# Port.net
KiCad netlist of a schematic drawn in Altium Designer
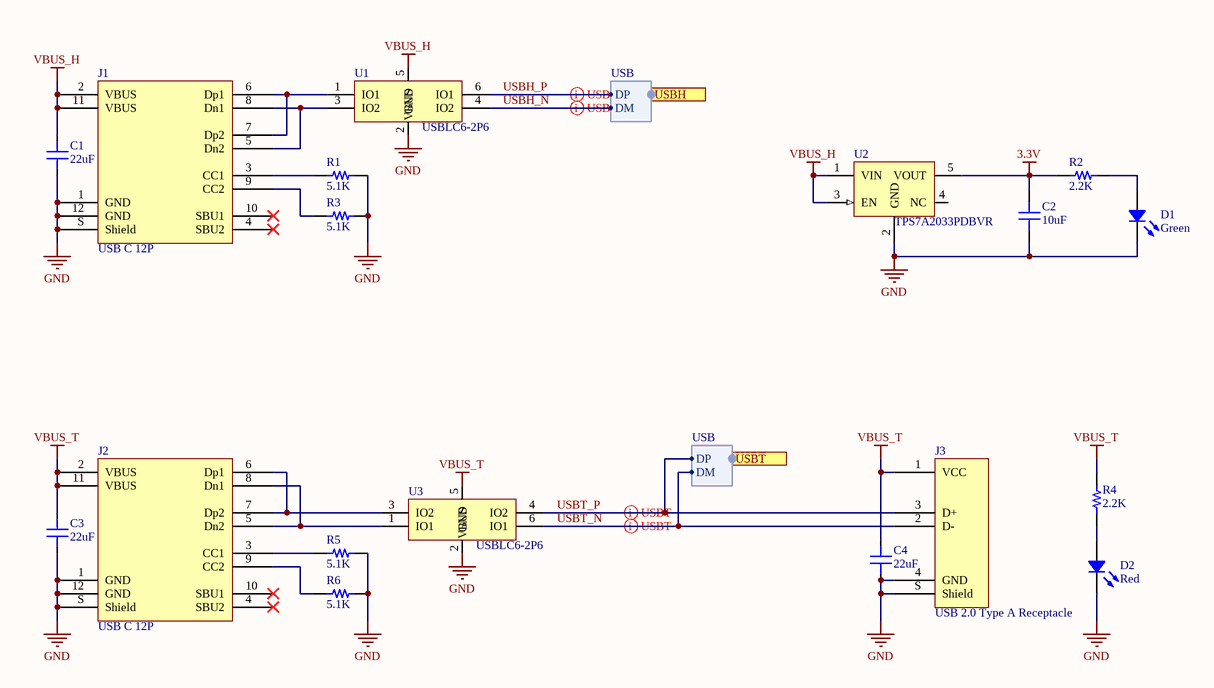
[diagram p0: Port.SchDoc]

(export (version "E")
  (design (tool "Eeschema 10.0.6"))
  (components
    (comp (ref "C1")
      (value "22uF")
      (footprint "CAP 0805/2012")
      (description "CAP CER 22UF 10V X5R 0805")
      (fields (field (name "PART NUMBER") "GRM219R61A226MEA0D") (field (name "MANUFACTURER") "Murata"))
      (libsource (lib "Mengsklib") (part "Capacitor"))
    )
    (comp (ref "C2")
      (value "10uF")
      (footprint "CAP 0603/1608")
      (description "CAP CER 10UF 25V X5R 0603")
      (fields (field (name "PART NUMBER") "GRM188R61E106MA73D") (field (name "MANUFACTURER") "Murata"))
      (libsource (lib "") (part "Capacitor_1"))
    )
    (comp (ref "C3")
      (value "22uF")
      (footprint "CAP 0805/2012")
      (description "CAP CER 22UF 10V X5R 0805")
      (fields (field (name "PART NUMBER") "GRM219R61A226MEA0D") (field (name "MANUFACTURER") "Murata"))
      (libsource (lib "Mengsklib") (part "Capacitor"))
    )
    (comp (ref "C4")
      (value "22uF")
      (footprint "CAP 0805/2012")
      (description "CAP CER 22UF 10V X5R 0805")
      (fields (field (name "PART NUMBER") "GRM219R61A226MEA0D") (field (name "MANUFACTURER") "Murata"))
      (libsource (lib "Mengsklib") (part "Capacitor"))
    )
    (comp (ref "D1")
      (value "Green")
      (footprint "LED 0603/1608 GREEN")
      (description "LED GREEN CLEAR 0603 SMD")
      (fields
        (field (name "COLOUR") "Green")
        (field (name "PART NUMBER") "LTST-C191KGKT")
        (field (name "MANUFACTURER") "Lite-On Inc.")
      )
      (libsource (lib "Mengsklib") (part "LED"))
    )
    (comp (ref "D2")
      (value "Red")
      (footprint "LED 0603/1608 RED")
      (description "LED RED CLEAR 0603 SMD")
      (fields
        (field (name "COLOUR") "Red")
        (field (name "PART NUMBER") "LTST-C191KRKT")
        (field (name "MANUFACTURER") "Lite-On Inc.")
      )
      (libsource (lib "Mengsklib") (part "LED"))
    )
    (comp (ref "J1")
      (value "USB C 12P")
      (footprint "JAE USB DX07S016JA1R1500")
      (description "USB 2.0 Type C, Receptacle, Horizontal, SMT")
      (fields (field (name "PART NUMBER") "DX07S016JA1R1500") (field (name "MANUFACTURER") "JAE"))
      (libsource (lib "Mengsklib") (part "JAE USB 2.0 Type C 12P"))
    )
    (comp (ref "J2")
      (value "USB C 12P")
      (footprint "JAE USB DX07S016JA1R1500")
      (description "USB 2.0 Type C, Receptacle, Horizontal, SMT")
      (fields (field (name "PART NUMBER") "DX07S016JA1R1500") (field (name "MANUFACTURER") "JAE"))
      (libsource (lib "Mengsklib") (part "JAE USB 2.0 Type C 12P"))
    )
    (comp (ref "J3")
      (value "USB 2.0 Type A Receptacle")
      (footprint "629104151021")
      (description "USB 2.0 Type A, Receptacle, Horizontal, SMT, with Pegs")
      (fields (field (name "PART NUMBER") "629104151021") (field (name "MANUFACTURER") "Wurth"))
      (libsource (lib "Mengsklib") (part "USB 2.0 Type A/B"))
    )
    (comp (ref "R1")
      (value "5.1K")
      (footprint "RES 0402/1005")
      (description "RES SMD 5.1K OHM 1% 1/16W 0402")
      (fields (field (name "PART NUMBER") "RC0402FR-075K1L") (field (name "MANUFACTURER") "Yageo"))
      (libsource (lib "Mengsklib") (part "Resistor"))
    )
    (comp (ref "R2")
      (value "2.2K")
      (footprint "RES 0402/1005")
      (description "RES SMD 2.2K OHM 1% 1/16W 0402")
      (fields (field (name "PART NUMBER") "RC0402FR-072K2L") (field (name "MANUFACTURER") "Yageo"))
      (libsource (lib "Mengsklib") (part "Resistor"))
    )
    (comp (ref "R3")
      (value "5.1K")
      (footprint "RES 0402/1005")
      (description "RES SMD 5.1K OHM 1% 1/16W 0402")
      (fields (field (name "PART NUMBER") "RC0402FR-075K1L") (field (name "MANUFACTURER") "Yageo"))
      (libsource (lib "Mengsklib") (part "Resistor"))
    )
    (comp (ref "R4")
      (value "2.2K")
      (footprint "RES 0402/1005")
      (description "RES SMD 2.2K OHM 1% 1/16W 0402")
      (fields (field (name "PART NUMBER") "RC0402FR-072K2L") (field (name "MANUFACTURER") "Yageo"))
      (libsource (lib "Mengsklib") (part "Resistor"))
    )
    (comp (ref "R5")
      (value "5.1K")
      (footprint "RES 0402/1005")
      (description "RES SMD 5.1K OHM 1% 1/16W 0402")
      (fields (field (name "PART NUMBER") "RC0402FR-075K1L") (field (name "MANUFACTURER") "Yageo"))
      (libsource (lib "Mengsklib") (part "Resistor"))
    )
    (comp (ref "R6")
      (value "5.1K")
      (footprint "RES 0402/1005")
      (description "RES SMD 5.1K OHM 1% 1/16W 0402")
      (fields (field (name "PART NUMBER") "RC0402FR-075K1L") (field (name "MANUFACTURER") "Yageo"))
      (libsource (lib "Mengsklib") (part "Resistor"))
    )
    (comp (ref "U1")
      (value "USBLC6-2P6")
      (footprint "SOTFL50P160X60-6N")
      (description "TVS ARRAY SOT666")
      (fields (field (name "MANUFACTURER") "ST"))
      (libsource (lib "") (part "USBLC6-2_1"))
    )
    (comp (ref "U2")
      (value "TPS7A2033PDBVR")
      (footprint "SOT95P280X110-5N")
      (description "LDO 3.3V 300MA SOT23-5")
      (fields (field (name "MANUFACTURER") "TI"))
      (libsource (lib "Mengsklib") (part "REG_5PIN_NC"))
    )
    (comp (ref "U3")
      (value "USBLC6-2P6")
      (footprint "SOTFL50P160X60-6N")
      (description "TVS ARRAY SOT666")
      (fields (field (name "MANUFACTURER") "ST"))
      (libsource (lib "Mengsklib") (part "USBLC6-2"))
    )
  )
  (nets
    (net (code "2") (name "/USBH_N") (class "Default")
      (node (ref "U1") (pin "4") (pinfunction "IO2_4") (pintype "passive"))
    )
    (net (code "3") (name "/USBH_P") (class "Default")
      (node (ref "U1") (pin "6") (pinfunction "IO1_6") (pintype "passive"))
    )
    (net (code "4") (name "/USBT_N") (class "Default")
      (node (ref "J3") (pin "2") (pinfunction "D-_2") (pintype "passive"))
      (node (ref "U3") (pin "6") (pinfunction "IO1_6") (pintype "passive"))
    )
    (net (code "5") (name "/USBT_P") (class "Default")
      (node (ref "J3") (pin "3") (pinfunction "D+_3") (pintype "passive"))
      (node (ref "U3") (pin "4") (pinfunction "IO2_4") (pintype "passive"))
    )
    (net (code "7") (name "3.3V") (class "Default")
      (node (ref "C2") (pin "2") (pinfunction "2_2") (pintype "passive"))
      (node (ref "R2") (pin "2") (pinfunction "2_2") (pintype "passive"))
      (node (ref "U2") (pin "5") (pinfunction "VOUT_5") (pintype "power_in"))
    )
    (net (code "8") (name "GND") (class "Default")
      (node (ref "C1") (pin "1") (pinfunction "1_1") (pintype "passive"))
      (node (ref "C2") (pin "1") (pinfunction "1_1") (pintype "passive"))
      (node (ref "C3") (pin "1") (pinfunction "1_1") (pintype "passive"))
      (node (ref "C4") (pin "1") (pinfunction "1_1") (pintype "passive"))
      (node (ref "D1") (pin "2") (pinfunction "2_2") (pintype "passive"))
      (node (ref "D2") (pin "2") (pinfunction "2_2") (pintype "passive"))
      (node (ref "J1") (pin "1") (pinfunction "GND_1") (pintype "passive"))
      (node (ref "J1") (pin "12") (pinfunction "GND_12") (pintype "passive"))
      (node (ref "J1") (pin "S") (pinfunction "Shield_S") (pintype "passive"))
      (node (ref "J2") (pin "1") (pinfunction "GND_1") (pintype "passive"))
      (node (ref "J2") (pin "12") (pinfunction "GND_12") (pintype "passive"))
      (node (ref "J2") (pin "S") (pinfunction "Shield_S") (pintype "passive"))
      (node (ref "J3") (pin "4") (pinfunction "GND_4") (pintype "passive"))
      (node (ref "J3") (pin "S") (pinfunction "Shield_S") (pintype "passive"))
      (node (ref "R1") (pin "1") (pinfunction "1_1") (pintype "passive"))
      (node (ref "R3") (pin "1") (pinfunction "1_1") (pintype "passive"))
      (node (ref "R5") (pin "1") (pinfunction "1_1") (pintype "passive"))
      (node (ref "R6") (pin "1") (pinfunction "1_1") (pintype "passive"))
      (node (ref "U1") (pin "2") (pinfunction "GND_2") (pintype "passive"))
      (node (ref "U2") (pin "2") (pinfunction "GND_2") (pintype "power_in"))
      (node (ref "U3") (pin "2") (pinfunction "GND_2") (pintype "passive"))
    )
    (net (code "9") (name "Net-(D1-Pad1)") (class "Default")
      (node (ref "D1") (pin "1") (pinfunction "1_1") (pintype "passive"))
      (node (ref "R2") (pin "1") (pinfunction "1_1") (pintype "passive"))
    )
    (net (code "10") (name "Net-(D2-Pad1)") (class "Default")
      (node (ref "D2") (pin "1") (pinfunction "1_1") (pintype "passive"))
      (node (ref "R4") (pin "2") (pinfunction "2_2") (pintype "passive"))
    )
    (net (code "11") (name "Net-(J1-CC1)") (class "Default")
      (node (ref "J1") (pin "3") (pinfunction "CC1_3") (pintype "passive"))
      (node (ref "R1") (pin "2") (pinfunction "2_2") (pintype "passive"))
    )
    (net (code "12") (name "Net-(J1-CC2)") (class "Default")
      (node (ref "J1") (pin "9") (pinfunction "CC2_9") (pintype "passive"))
      (node (ref "R3") (pin "2") (pinfunction "2_2") (pintype "passive"))
    )
    (net (code "13") (name "Net-(J1-Dn1)") (class "Default")
      (node (ref "J1") (pin "5") (pinfunction "Dn2_5") (pintype "passive"))
      (node (ref "J1") (pin "8") (pinfunction "Dn1_8") (pintype "passive"))
      (node (ref "U1") (pin "3") (pinfunction "IO2_3") (pintype "passive"))
    )
    (net (code "14") (name "Net-(J1-Dp1)") (class "Default")
      (node (ref "J1") (pin "6") (pinfunction "Dp1_6") (pintype "passive"))
      (node (ref "J1") (pin "7") (pinfunction "Dp2_7") (pintype "passive"))
      (node (ref "U1") (pin "1") (pinfunction "IO1_1") (pintype "passive"))
    )
    (net (code "15") (name "Net-(J2-CC1)") (class "Default")
      (node (ref "J2") (pin "3") (pinfunction "CC1_3") (pintype "passive"))
      (node (ref "R5") (pin "2") (pinfunction "2_2") (pintype "passive"))
    )
    (net (code "16") (name "Net-(J2-CC2)") (class "Default")
      (node (ref "J2") (pin "9") (pinfunction "CC2_9") (pintype "passive"))
      (node (ref "R6") (pin "2") (pinfunction "2_2") (pintype "passive"))
    )
    (net (code "17") (name "Net-(J2-Dn1)") (class "Default")
      (node (ref "J2") (pin "5") (pinfunction "Dn2_5") (pintype "passive"))
      (node (ref "J2") (pin "8") (pinfunction "Dn1_8") (pintype "passive"))
      (node (ref "U3") (pin "1") (pinfunction "IO1_1") (pintype "passive"))
    )
    (net (code "18") (name "Net-(J2-Dp1)") (class "Default")
      (node (ref "J2") (pin "6") (pinfunction "Dp1_6") (pintype "passive"))
      (node (ref "J2") (pin "7") (pinfunction "Dp2_7") (pintype "passive"))
      (node (ref "U3") (pin "3") (pinfunction "IO2_3") (pintype "passive"))
    )
    (net (code "19") (name "VBUS_H") (class "Default")
      (node (ref "C1") (pin "2") (pinfunction "2_2") (pintype "passive"))
      (node (ref "J1") (pin "11") (pinfunction "VBUS_11") (pintype "passive"))
      (node (ref "J1") (pin "2") (pinfunction "VBUS_2") (pintype "passive"))
      (node (ref "U1") (pin "5") (pinfunction "VBUS_5") (pintype "passive"))
      (node (ref "U2") (pin "1") (pinfunction "VIN_1") (pintype "power_in"))
      (node (ref "U2") (pin "3") (pinfunction "EN_3") (pintype "input"))
    )
    (net (code "20") (name "VBUS_T") (class "Default")
      (node (ref "C3") (pin "2") (pinfunction "2_2") (pintype "passive"))
      (node (ref "C4") (pin "2") (pinfunction "2_2") (pintype "passive"))
      (node (ref "J2") (pin "11") (pinfunction "VBUS_11") (pintype "passive"))
      (node (ref "J2") (pin "2") (pinfunction "VBUS_2") (pintype "passive"))
      (node (ref "J3") (pin "1") (pinfunction "VCC_1") (pintype "passive"))
      (node (ref "R4") (pin "1") (pinfunction "1_1") (pintype "passive"))
      (node (ref "U3") (pin "5") (pinfunction "VBUS_5") (pintype "passive"))
    )
    (net (code "21") (name "unconnected-(J1-SBU1-Pad10)") (class "Default")
      (node (ref "J1") (pin "10") (pinfunction "SBU1_10") (pintype "passive+no_connect"))
    )
    (net (code "22") (name "unconnected-(J1-SBU2-Pad4)") (class "Default")
      (node (ref "J1") (pin "4") (pinfunction "SBU2_4") (pintype "passive+no_connect"))
    )
    (net (code "23") (name "unconnected-(J2-SBU1-Pad10)") (class "Default")
      (node (ref "J2") (pin "10") (pinfunction "SBU1_10") (pintype "passive+no_connect"))
    )
    (net (code "24") (name "unconnected-(J2-SBU2-Pad4)") (class "Default")
      (node (ref "J2") (pin "4") (pinfunction "SBU2_4") (pintype "passive+no_connect"))
    )
    (net (code "25") (name "unconnected-(U2-NC-Pad4)") (class "Default")
      (node (ref "U2") (pin "4") (pinfunction "NC_4") (pintype "passive"))
    )
  )
)
